# Main.net
KiCad netlist of a schematic drawn in Altium Designer
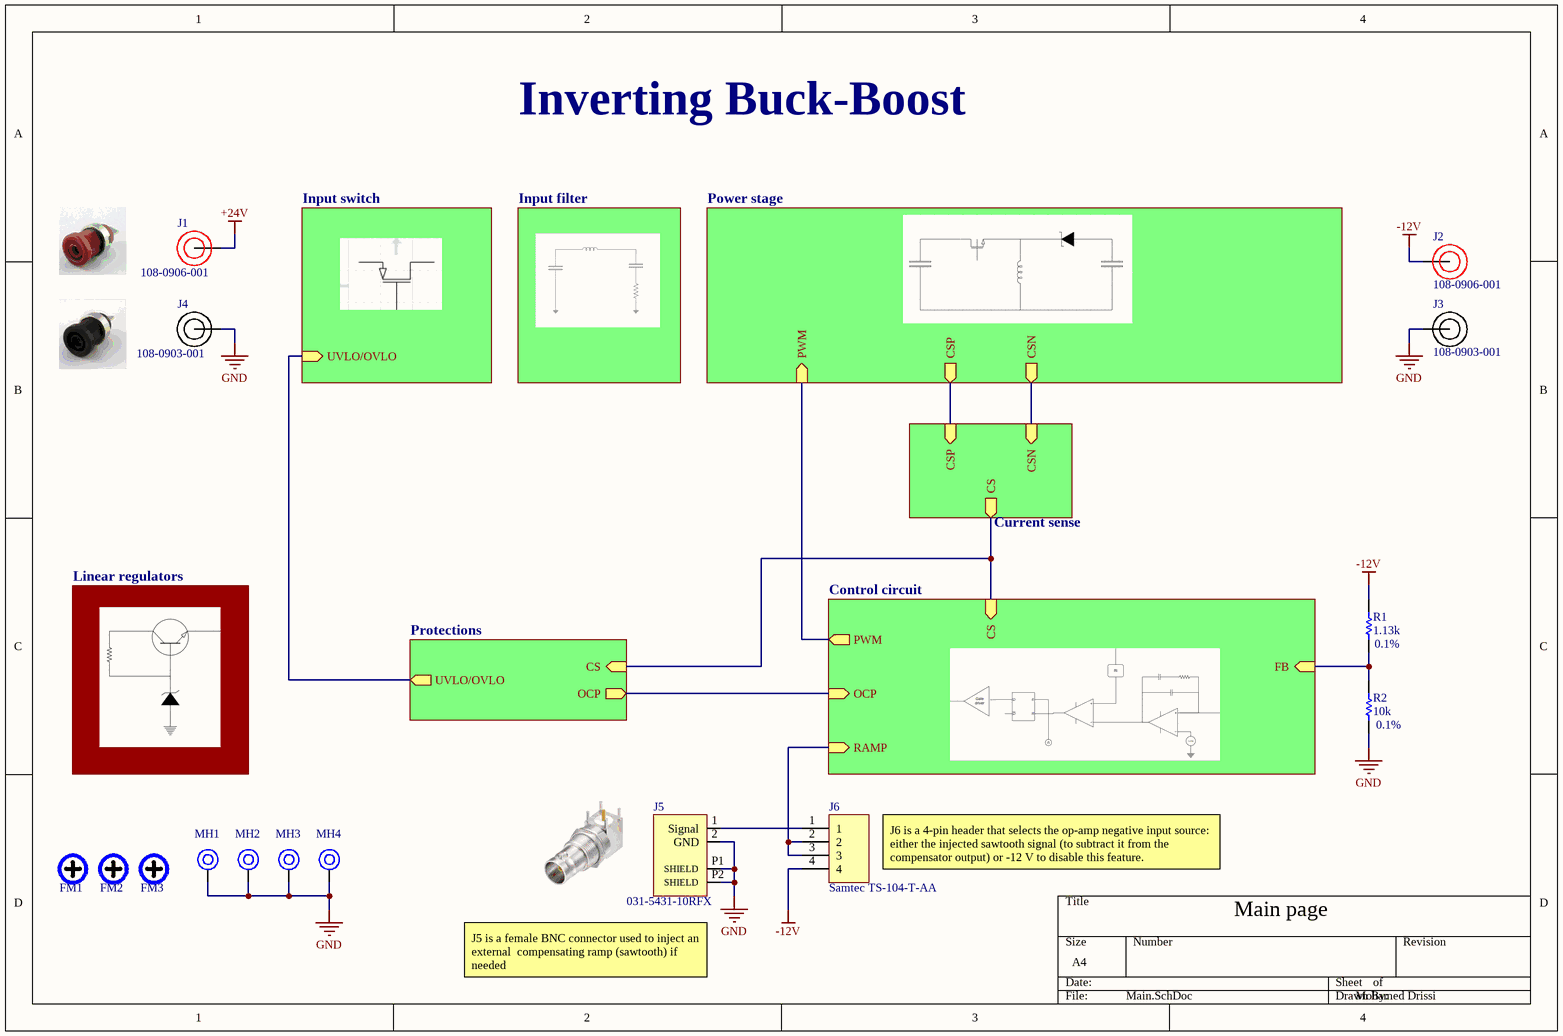
[diagram p0: Main.SchDoc]

(export (version "E")
  (design (tool "Eeschema 10.0.6"))
  (components
    (comp (ref "FM1")
      (value "Fiducial Marker")
      (footprint "FIDUCIAL_CROSS_1MM5")
      (description "Fiducial Marker Cross 1.5mm NO BOM")
      (libsource (lib "Schematic-Lib-PhilsLab") (part "FIDUCIAL_CROSS_1MM5"))
    )
    (comp (ref "FM2")
      (value "Fiducial Marker")
      (footprint "FIDUCIAL_CROSS_1MM5")
      (description "Fiducial Marker Cross 1.5mm NO BOM")
      (libsource (lib "Schematic-Lib-PhilsLab") (part "FIDUCIAL_CROSS_1MM5"))
    )
    (comp (ref "FM3")
      (value "Fiducial Marker")
      (footprint "FIDUCIAL_CROSS_1MM5")
      (description "Fiducial Marker Cross 1.5mm NO BOM")
      (libsource (lib "Schematic-Lib-PhilsLab") (part "FIDUCIAL_CROSS_1MM5"))
    )
    (comp (ref "J1")
      (value "108-0906-001")
      (footprint "Black Banana connector Solder terminal")
      (description "Right-angle Dual Port D-Sub Connector")
      (fields (field (name "MANUFACTURER") "Cinch Connectivity Solutions"))
      (libsource (lib "Inverting buck boost") (part "Cinch 108-0906-001"))
    )
    (comp (ref "J2")
      (value "108-0906-001")
      (footprint "Black Banana connector Solder terminal")
      (description "Right-angle Dual Port D-Sub Connector")
      (fields (field (name "MANUFACTURER") "Cinch Connectivity Solutions"))
      (libsource (lib "Inverting buck boost") (part "Cinch 108-0906-001"))
    )
    (comp (ref "J3")
      (value "108-0903-001")
      (footprint "Black Banana connector Solder terminal")
      (description "Banana Test Connector, 4mm, Jack, Panel Mount, 15 A, 7 kV, Tin Plated Contacts, Black")
      (fields (field (name "MANUFACTURER") "Cinch Connectivity Solutions"))
      (libsource (lib "Inverting buck boost") (part "Cinch 108-0903-001"))
    )
    (comp (ref "J4")
      (value "108-0903-001")
      (footprint "Black Banana connector Solder terminal")
      (description "Banana Test Connector, 4mm, Jack, Panel Mount, 15 A, 7 kV, Tin Plated Contacts, Black")
      (fields (field (name "MANUFACTURER") "Cinch Connectivity Solutions"))
      (libsource (lib "Inverting buck boost") (part "Cinch 108-0903-001"))
    )
    (comp (ref "J5")
      (value "031-5431-10RFX")
      (footprint "031-5431-10RFX BNC")
      (description "RF BNC Connector, Female, Panel Mount, Board And Panel Mount, Solder Terminal, Jack")
      (fields (field (name "MANUFACTURER") "Amphenol RF"))
      (libsource (lib "Inverting buck boost") (part "Amphenol 031-5431-10RFX"))
    )
    (comp (ref "J6")
      (value "Samtec TS-104-T-AA")
      (footprint "CONN HEADER VERT 4POS 2.54MM")
      (description "Pin Header, Precision Machined Terminal, Board-to-Board, 2.54 mm, 1 Rows, 4 Contacts, Through Hole")
      (fields (field (name "MANUFACTURER") "Samtec") (field (name "MANUFACTURER PART NUMBER") "TS-104-T-AA"))
      (libsource (lib "Inverting buck boost") (part "Samtec TS-104-T-AA"))
    )
    (comp (ref "MH1")
      (value "Mounting Hole")
      (footprint "MOUNTING")
      (fields (field (name "MANUFACTURER PART NUMBER") "NA"))
      (libsource (lib "COB with RK3399") (part "MH_3.5H_6D"))
    )
    (comp (ref "MH2")
      (value "Mounting Hole")
      (footprint "MOUNTING")
      (fields (field (name "MANUFACTURER PART NUMBER") "NA"))
      (libsource (lib "COB with RK3399") (part "MH_3.5H_6D"))
    )
    (comp (ref "MH3")
      (value "Mounting Hole")
      (footprint "MOUNTING")
      (fields (field (name "MANUFACTURER PART NUMBER") "NA"))
      (libsource (lib "COB with RK3399") (part "MH_3.5H_6D"))
    )
    (comp (ref "MH4")
      (value "Mounting Hole")
      (footprint "MOUNTING")
      (fields (field (name "MANUFACTURER PART NUMBER") "NA"))
      (libsource (lib "COB with RK3399") (part "MH_3.5H_6D"))
    )
    (comp (ref "R1")
      (value "RT0603BRD071K13L")
      (footprint "RES_0603")
      (description "Res Thin Film 0603 1.13K Ohm 0.1% 0.1W(1/10W) ±25ppm/C Pad SMD T/R")
      (fields
        (field (name "MANUFACTURER") "Yageo Group")
        (field (name "TOLERANCE") "0.1%")
        (field (name "RESISTANCE") "1.13k")
      )
      (libsource (lib "Inverting buck boost") (part "Panasonic RT0603BRD071K13L"))
    )
    (comp (ref "R2")
      (value "ERA-3AEB103V")
      (footprint "res_0603")
      (description "Res Thin Film 0603 10K Ohm 0.1% 1/10W ±25ppm/°C Molded SMD SMD Punched Carrier T/R")
      (fields
        (field (name "MANUFACTURER") "Panasonic")
        (field (name "TOLERANCE") "0.1%")
        (field (name "RESISTANCE") "10k")
      )
      (libsource (lib "Inverting buck boost") (part "Panasonic ERA-3AEB103V"))
    )
  )
  (nets
    (net (code "1") (name "+24V") (class "Default")
      (node (ref "J1") (pin "1") (pinfunction "1_1") (pintype "passive"))
    )
    (net (code "2") (name "-12V") (class "Default")
      (node (ref "J2") (pin "1") (pinfunction "1_1") (pintype "passive"))
      (node (ref "J6") (pin "4") (pinfunction "4_4") (pintype "passive"))
      (node (ref "R1") (pin "2") (pinfunction "2_2") (pintype "passive"))
    )
    (net (code "6") (name "/FB") (class "Default")
      (node (ref "R1") (pin "1") (pinfunction "1_1") (pintype "passive"))
      (node (ref "R2") (pin "2") (pinfunction "2_2") (pintype "passive"))
    )
    (net (code "9") (name "/RAMP") (class "Default")
      (node (ref "J6") (pin "2") (pinfunction "2_2") (pintype "passive"))
      (node (ref "J6") (pin "3") (pinfunction "3_3") (pintype "passive"))
    )
    (net (code "11") (name "GND") (class "Default")
      (node (ref "J3") (pin "1") (pinfunction "1_1") (pintype "passive"))
      (node (ref "J4") (pin "1") (pinfunction "1_1") (pintype "passive"))
      (node (ref "J5") (pin "2") (pinfunction "GND_2") (pintype "passive"))
      (node (ref "J5") (pin "P1") (pinfunction "SHIELD_P1") (pintype "passive"))
      (node (ref "J5") (pin "P2") (pinfunction "SHIELD_P2") (pintype "passive"))
      (node (ref "MH1") (pin "1") (pinfunction "1_1") (pintype "passive"))
      (node (ref "MH2") (pin "1") (pinfunction "1_1") (pintype "passive"))
      (node (ref "MH3") (pin "1") (pinfunction "1_1") (pintype "passive"))
      (node (ref "MH4") (pin "1") (pinfunction "1_1") (pintype "passive"))
      (node (ref "R2") (pin "1") (pinfunction "1_1") (pintype "passive"))
    )
    (net (code "12") (name "Net-(J5-Signal)") (class "Default")
      (node (ref "J5") (pin "1") (pinfunction "Signal_1") (pintype "passive"))
      (node (ref "J6") (pin "1") (pinfunction "1_1") (pintype "passive"))
    )
  )
)
